# 09-USBUart_PPSMUX_UARTMUX.net
KiCad netlist of a schematic drawn in Altium Designer
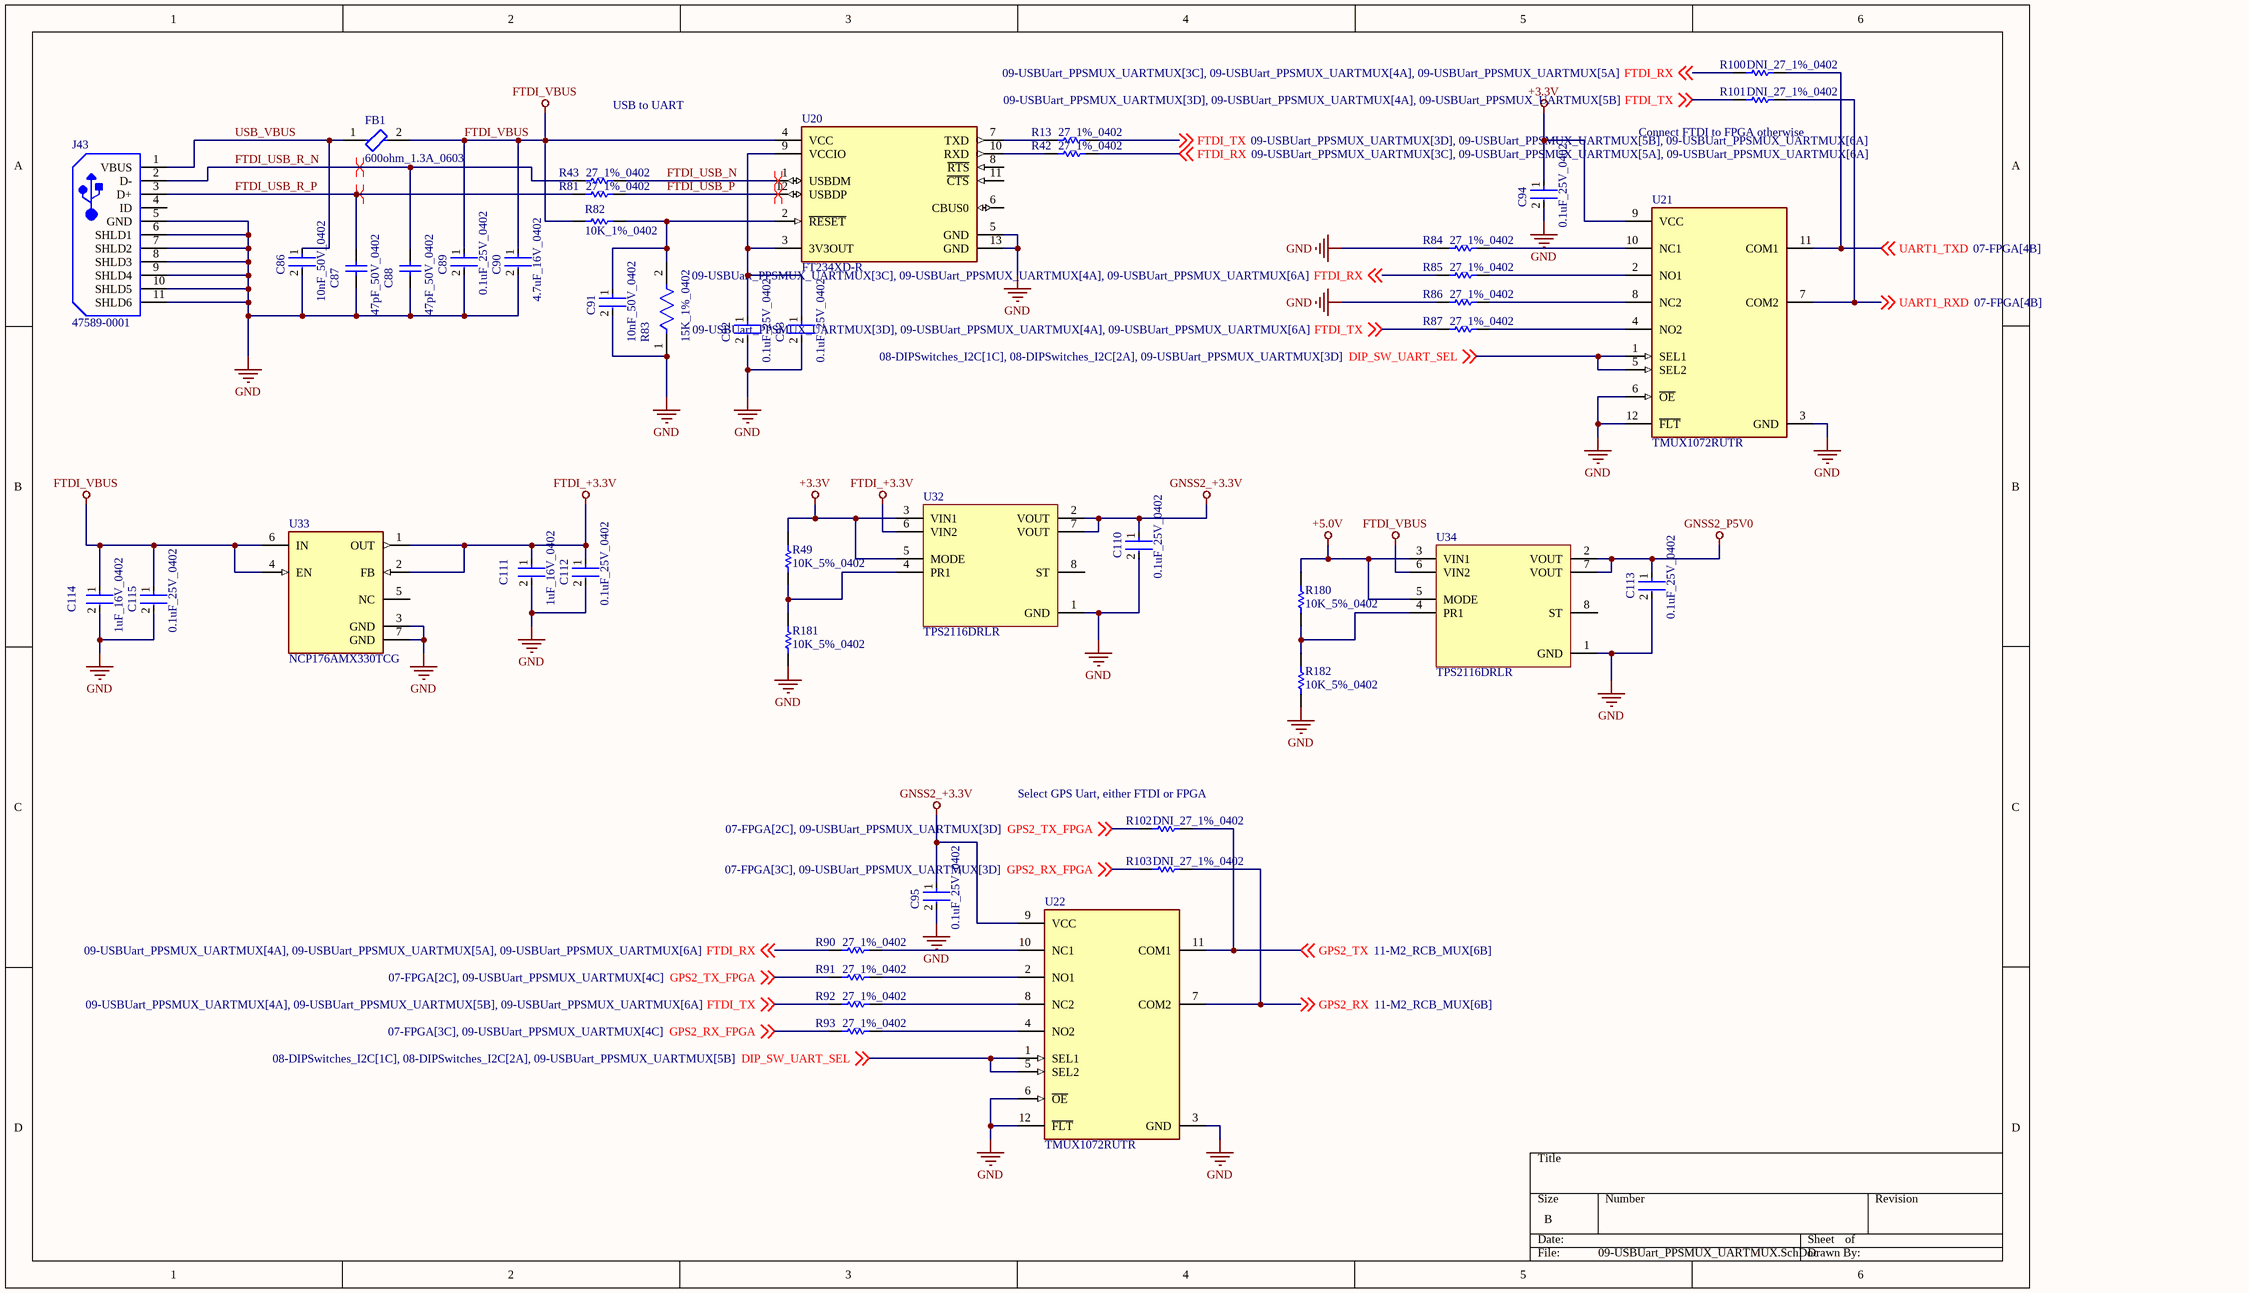
[diagram p0: 09-USBUart_PPSMUX_UARTMUX.SchDoc]

(export (version "E")
  (design (tool "Eeschema 10.0.6"))
  (components
    (comp (ref "C86")
      (value "10nF_50V_0402")
      (footprint "FP-CC0402-MFG")
      (description "CAP CER 10000PF 50V X7R 0402")
      (fields
        (field (name "OCTOPART") "https://octopart.com/cc0402krx7r9bb103-yageo-8376513")
        (field (name "MANUFACTURER PART NUMBER") "CC0402KRX7R9BB103")
      )
      (libsource (lib "Altium Content Vault") (part "11868f565c42a9108669ba33697ecf6"))
    )
    (comp (ref "C87")
      (value "47pF_50V_0402")
      (footprint "CAPC1005X55X25LL05T10")
      (fields (field (name "PART NUMBER") "GRM1555C1H470JA01D") (field (name "MANUFACTURER") "Murata"))
      (libsource (lib "Altium Content Vault") (part "CAP"))
    )
    (comp (ref "C88")
      (value "47pF_50V_0402")
      (footprint "CAPC1005X55X25LL05T10")
      (fields (field (name "PART NUMBER") "GRM1555C1H470JA01D") (field (name "MANUFACTURER") "Murata"))
      (libsource (lib "Altium Content Vault") (part "CAP"))
    )
    (comp (ref "C89")
      (value "0.1uF_25V_0402")
      (footprint "FP-0402-L_1_0_1-W_0_5_0_1-IPC_C")
      (description "General Purpose Ceramic Capacitor, 0402, 100nF, 10%, X7R, 15%, 25V")
      (fields (field (name "VOLTAGE") "25V") (field (name "TOLERANCE") "10%"))
      (libsource (lib "Altium Content Vault") (part "b4654b650e69147ec39a6b967a45e02"))
    )
    (comp (ref "C90")
      (value "4.7uF_16V_0402")
      (footprint "FP-CL829-IPC_C")
      (description "Cap Ceramic 4.7uF 16V X5R ±20% SMD 0402 +85°C Paper T/R")
      (fields (field (name "TOLERANCE") "20%"))
      (libsource (lib "Altium Content Vault") (part "b4654b650e69147ec39a6b967a45e02"))
    )
    (comp (ref "C91")
      (value "10nF_50V_0402")
      (footprint "FP-CC0402-MFG")
      (description "CAP CER 10000PF 50V X7R 0402")
      (fields
        (field (name "OCTOPART") "https://octopart.com/cc0402krx7r9bb103-yageo-8376513")
        (field (name "MANUFACTURER PART NUMBER") "CC0402KRX7R9BB103")
      )
      (libsource (lib "Altium Content Vault") (part "11868f565c42a9108669ba33697ecf6"))
    )
    (comp (ref "C92")
      (value "0.1uF_25V_0402")
      (footprint "FP-0402-L_1_0_1-W_0_5_0_1-IPC_C")
      (description "General Purpose Ceramic Capacitor, 0402, 100nF, 10%, X7R, 15%, 25V")
      (fields (field (name "VOLTAGE") "25V") (field (name "TOLERANCE") "10%"))
      (libsource (lib "Altium Content Vault") (part "b4654b650e69147ec39a6b967a45e02"))
    )
    (comp (ref "C93")
      (value "0.1uF_25V_0402")
      (footprint "FP-0402-L_1_0_1-W_0_5_0_1-IPC_C")
      (description "General Purpose Ceramic Capacitor, 0402, 100nF, 10%, X7R, 15%, 25V")
      (fields (field (name "VOLTAGE") "25V") (field (name "TOLERANCE") "10%"))
      (libsource (lib "Altium Content Vault") (part "b4654b650e69147ec39a6b967a45e02"))
    )
    (comp (ref "C94")
      (value "0.1uF_25V_0402")
      (footprint "FP-0402-L_1_0_1-W_0_5_0_1-IPC_C")
      (description "General Purpose Ceramic Capacitor, 0402, 100nF, 10%, X7R, 15%, 25V")
      (fields (field (name "VOLTAGE") "25V") (field (name "TOLERANCE") "10%"))
      (libsource (lib "Altium Content Vault") (part "b4654b650e69147ec39a6b967a45e02"))
    )
    (comp (ref "C95")
      (value "0.1uF_25V_0402")
      (footprint "FP-0402-L_1_0_1-W_0_5_0_1-IPC_C")
      (description "General Purpose Ceramic Capacitor, 0402, 100nF, 10%, X7R, 15%, 25V")
      (fields (field (name "VOLTAGE") "25V") (field (name "TOLERANCE") "10%"))
      (libsource (lib "Altium Content Vault") (part "b4654b650e69147ec39a6b967a45e02"))
    )
    (comp (ref "C110")
      (value "0.1uF_25V_0402")
      (footprint "FP-0402-L_1_0_1-W_0_5_0_1-IPC_C")
      (description "General Purpose Ceramic Capacitor, 0402, 100nF, 10%, X7R, 15%, 25V")
      (fields (field (name "VOLTAGE") "25V") (field (name "TOLERANCE") "10%"))
      (libsource (lib "Altium Content Vault") (part "b4654b650e69147ec39a6b967a45e02"))
    )
    (comp (ref "C111")
      (value "1uF_16V_0402")
      (footprint "FP-0402-L_1_0_0_05-W_0_5-IPC_A")
      (description "None")
      (fields (field (name "TOLERANCE") "10%"))
      (libsource (lib "Altium Content Vault") (part "b4654b650e69147ec39a6b967a45e02"))
    )
    (comp (ref "C112")
      (value "0.1uF_25V_0402")
      (footprint "FP-0402-L_1_0_1-W_0_5_0_1-IPC_C")
      (description "General Purpose Ceramic Capacitor, 0402, 100nF, 10%, X7R, 15%, 25V")
      (fields (field (name "VOLTAGE") "25V") (field (name "TOLERANCE") "10%"))
      (libsource (lib "Altium Content Vault") (part "b4654b650e69147ec39a6b967a45e02"))
    )
    (comp (ref "C113")
      (value "0.1uF_25V_0402")
      (footprint "FP-0402-L_1_0_1-W_0_5_0_1-IPC_C")
      (description "General Purpose Ceramic Capacitor, 0402, 100nF, 10%, X7R, 15%, 25V")
      (fields (field (name "VOLTAGE") "25V") (field (name "TOLERANCE") "10%"))
      (libsource (lib "Altium Content Vault") (part "b4654b650e69147ec39a6b967a45e02"))
    )
    (comp (ref "C114")
      (value "1uF_16V_0402")
      (footprint "FP-0402-L_1_0_0_05-W_0_5-IPC_A")
      (description "None")
      (fields (field (name "TOLERANCE") "10%"))
      (libsource (lib "Altium Content Vault") (part "b4654b650e69147ec39a6b967a45e02"))
    )
    (comp (ref "C115")
      (value "0.1uF_25V_0402")
      (footprint "FP-0402-L_1_0_1-W_0_5_0_1-IPC_C")
      (description "General Purpose Ceramic Capacitor, 0402, 100nF, 10%, X7R, 15%, 25V")
      (fields (field (name "VOLTAGE") "25V") (field (name "TOLERANCE") "10%"))
      (libsource (lib "Altium Content Vault") (part "b4654b650e69147ec39a6b967a45e02"))
    )
    (comp (ref "FB1")
      (value "600ohm_1.3A_0603")
      (footprint "FP-BLM18-0_15-t0_8-IPC_A")
      (description "Chip Ferrite Bead, 0603, 600Ω @ 100MHz, 0.15Ω, 25%, 1.3A")
      (fields (field (name "TOLERANCE") "25%"))
      (libsource (lib "Altium Content Vault") (part "5f30dd21d616792df468990f7003faa"))
    )
    (comp (ref "J43")
      (value "47589-0001")
      (footprint "MOLX-47589-0001_V")
      (description "Right Angle Female Type AB Micro USB Connector, 30 V, 1.8 A, -30 to 85 degC, RoHS, Tape and Reel")
      (fields (field (name "MANUFACTURER") "Molex"))
      (libsource (lib "Altium Content Vault") (part "USB-5-6SHLD"))
    )
    (comp (ref "R13")
      (value "27_1%_0402")
      (footprint "RESC1005X40X25NL05T05")
      (fields (field (name "PART NUMBER") "CRCW040227R0FKED") (field (name "MANUFACTURER") "Vishay Dale"))
      (libsource (lib "Altium Content Vault") (part "RES"))
    )
    (comp (ref "R42")
      (value "27_1%_0402")
      (footprint "RESC1005X40X25NL05T05")
      (fields (field (name "PART NUMBER") "CRCW040227R0FKED") (field (name "MANUFACTURER") "Vishay Dale"))
      (libsource (lib "Altium Content Vault") (part "RES"))
    )
    (comp (ref "R43")
      (value "27_1%_0402")
      (footprint "RESC1005X40X25NL05T05")
      (fields (field (name "PART NUMBER") "CRCW040227R0FKED") (field (name "MANUFACTURER") "Vishay Dale"))
      (libsource (lib "Altium Content Vault") (part "RES"))
    )
    (comp (ref "R49")
      (value "10K_5%_0402")
      (footprint "RESC1005X40X25ML05T05")
      (fields (field (name "PART NUMBER") "ERJ-2GEJ103X") (field (name "MANUFACTURER") "Panasonic"))
      (libsource (lib "Altium Content Vault") (part "RES"))
    )
    (comp (ref "R81")
      (value "27_1%_0402")
      (footprint "RESC1005X40X25NL05T05")
      (fields (field (name "PART NUMBER") "CRCW040227R0FKED") (field (name "MANUFACTURER") "Vishay Dale"))
      (libsource (lib "Altium Content Vault") (part "RES"))
    )
    (comp (ref "R82")
      (value "10K_1%_0402")
      (footprint "RESC1005X40X25LL05T10")
      (fields (field (name "PART NUMBER") "RC0402FR-0710KL") (field (name "MANUFACTURER") "Yageo / Phycomp"))
      (libsource (lib "Altium Content Vault") (part "RES"))
    )
    (comp (ref "R83")
      (value "15K_1%_0402")
      (footprint "FP-ERJ2R-MFG")
      (description "RES SMD 15K OHM 1% 1/10W 0402")
      (fields (field (name "TOLERANCE") "1%") (field (name "MANUFACTURER PART NUMBER") "ERJ-2RKF1502X"))
      (libsource (lib "Altium Content Vault") (part "1029c3af85768c4190bb7ad29bc67b5"))
    )
    (comp (ref "R84")
      (value "27_1%_0402")
      (footprint "RESC1005X40X25NL05T05")
      (fields (field (name "PART NUMBER") "CRCW040227R0FKED") (field (name "MANUFACTURER") "Vishay Dale"))
      (libsource (lib "Altium Content Vault") (part "RES"))
    )
    (comp (ref "R85")
      (value "27_1%_0402")
      (footprint "RESC1005X40X25NL05T05")
      (fields (field (name "PART NUMBER") "CRCW040227R0FKED") (field (name "MANUFACTURER") "Vishay Dale"))
      (libsource (lib "Altium Content Vault") (part "RES"))
    )
    (comp (ref "R86")
      (value "27_1%_0402")
      (footprint "RESC1005X40X25NL05T05")
      (fields (field (name "PART NUMBER") "CRCW040227R0FKED") (field (name "MANUFACTURER") "Vishay Dale"))
      (libsource (lib "Altium Content Vault") (part "RES"))
    )
    (comp (ref "R87")
      (value "27_1%_0402")
      (footprint "RESC1005X40X25NL05T05")
      (fields (field (name "PART NUMBER") "CRCW040227R0FKED") (field (name "MANUFACTURER") "Vishay Dale"))
      (libsource (lib "Altium Content Vault") (part "RES"))
    )
    (comp (ref "R90")
      (value "27_1%_0402")
      (footprint "RESC1005X40X25NL05T05")
      (fields (field (name "PART NUMBER") "CRCW040227R0FKED") (field (name "MANUFACTURER") "Vishay Dale"))
      (libsource (lib "Altium Content Vault") (part "RES"))
    )
    (comp (ref "R91")
      (value "27_1%_0402")
      (footprint "RESC1005X40X25NL05T05")
      (fields (field (name "PART NUMBER") "CRCW040227R0FKED") (field (name "MANUFACTURER") "Vishay Dale"))
      (libsource (lib "Altium Content Vault") (part "RES"))
    )
    (comp (ref "R92")
      (value "27_1%_0402")
      (footprint "RESC1005X40X25NL05T05")
      (fields (field (name "PART NUMBER") "CRCW040227R0FKED") (field (name "MANUFACTURER") "Vishay Dale"))
      (libsource (lib "Altium Content Vault") (part "RES"))
    )
    (comp (ref "R93")
      (value "27_1%_0402")
      (footprint "RESC1005X40X25NL05T05")
      (fields (field (name "PART NUMBER") "CRCW040227R0FKED") (field (name "MANUFACTURER") "Vishay Dale"))
      (libsource (lib "Altium Content Vault") (part "RES"))
    )
    (comp (ref "R100")
      (value "DNI_27_1%_0402")
      (footprint "RESC1005X40X25NL05T05")
      (fields (field (name "PART NUMBER") "CRCW040227R0FKED") (field (name "MANUFACTURER") "Vishay Dale"))
      (libsource (lib "Altium Content Vault") (part "RES"))
    )
    (comp (ref "R101")
      (value "DNI_27_1%_0402")
      (footprint "RESC1005X40X25NL05T05")
      (fields (field (name "PART NUMBER") "CRCW040227R0FKED") (field (name "MANUFACTURER") "Vishay Dale"))
      (libsource (lib "Altium Content Vault") (part "RES"))
    )
    (comp (ref "R102")
      (value "DNI_27_1%_0402")
      (footprint "RESC1005X40X25NL05T05")
      (fields (field (name "PART NUMBER") "CRCW040227R0FKED") (field (name "MANUFACTURER") "Vishay Dale"))
      (libsource (lib "Altium Content Vault") (part "RES"))
    )
    (comp (ref "R103")
      (value "DNI_27_1%_0402")
      (footprint "RESC1005X40X25NL05T05")
      (fields (field (name "PART NUMBER") "CRCW040227R0FKED") (field (name "MANUFACTURER") "Vishay Dale"))
      (libsource (lib "Altium Content Vault") (part "RES"))
    )
    (comp (ref "R180")
      (value "10K_5%_0402")
      (footprint "RESC1005X40X25ML05T05")
      (fields (field (name "PART NUMBER") "ERJ-2GEJ103X") (field (name "MANUFACTURER") "Panasonic"))
      (libsource (lib "Altium Content Vault") (part "RES"))
    )
    (comp (ref "R181")
      (value "10K_5%_0402")
      (footprint "RESC1005X40X25ML05T05")
      (fields (field (name "PART NUMBER") "ERJ-2GEJ103X") (field (name "MANUFACTURER") "Panasonic"))
      (libsource (lib "Altium Content Vault") (part "RES"))
    )
    (comp (ref "R182")
      (value "10K_5%_0402")
      (footprint "RESC1005X40X25ML05T05")
      (fields (field (name "PART NUMBER") "ERJ-2GEJ103X") (field (name "MANUFACTURER") "Panasonic"))
      (libsource (lib "Altium Content Vault") (part "RES"))
    )
    (comp (ref "U20")
      (value "FT234XD-R")
      (footprint "FP-DFN-12-IPC_B")
      (description "IC USB SERIAL BASIC UART 12DFN")
      (libsource (lib "Altium Content Vault") (part "4bef3367ed9f9051bcb84ab46edda1c"))
    )
    (comp (ref "U21")
      (value "TMUX1072RUTR")
      (footprint "FP-RUT0012A-MFG")
      (description "IC SWITCH SPDT DUAL 12UQFN")
      (libsource (lib "Altium Content Vault") (part "12a319ab100cd6cfe745e35972674f5"))
    )
    (comp (ref "U22")
      (value "TMUX1072RUTR")
      (footprint "FP-RUT0012A-MFG")
      (description "IC SWITCH SPDT DUAL 12UQFN")
      (libsource (lib "Altium Content Vault") (part "12a319ab100cd6cfe745e35972674f5"))
    )
    (comp (ref "U32")
      (value "TPS2116DRLR")
      (footprint "IC_TPS2116")
      (description "1.6-V to 5.5-V, 40-mΩ, 2.5-A, low-IQ, priority power multiplexer 8-SOT-5X3 -40 to 125")
      (fields (field (name "MF") "Texas Instruments"))
      (libsource (lib "LotusSound") (part "IC_TPS2116DRLR"))
    )
    (comp (ref "U33")
      (value "NCP176AMX330TCG")
      (footprint "FP-711AT-MFG")
      (description "IC REG LINEAR 3.3V 500MA 6XDFN")
      (fields
        (field (name "MANUFACTURER") "ON Semiconductor")
        (field (name "OCTOPART") "https://octopart.com/ncp176amx330tcg-on+semiconductor-61522616")
      )
      (libsource (lib "Altium Content Vault") (part "a38d0f79c2a9f01c07a7e52882ed186"))
    )
    (comp (ref "U34")
      (value "TPS2116DRLR")
      (footprint "IC_TPS2116")
      (description "1.6-V to 5.5-V, 40-mΩ, 2.5-A, low-IQ, priority power multiplexer 8-SOT-5X3 -40 to 125")
      (fields (field (name "MF") "Texas Instruments"))
      (libsource (lib "LotusSound") (part "IC_TPS2116DRLR"))
    )
  )
  (nets
    (net (code "1") (name "+3.3V") (class "Default")
      (node (ref "C94") (pin "1") (pinfunction "1_1") (pintype "passive"))
      (node (ref "R49") (pin "2") (pinfunction "2_2") (pintype "passive"))
      (node (ref "U21") (pin "9") (pinfunction "VCC_9") (pintype "power_in"))
      (node (ref "U32") (pin "3") (pinfunction "VIN1_3") (pintype "passive"))
      (node (ref "U32") (pin "5") (pinfunction "MODE_5") (pintype "passive"))
    )
    (net (code "2") (name "+5.0V") (class "Default")
      (node (ref "R180") (pin "2") (pinfunction "2_2") (pintype "passive"))
      (node (ref "U34") (pin "3") (pinfunction "VIN1_3") (pintype "passive"))
      (node (ref "U34") (pin "5") (pinfunction "MODE_5") (pintype "passive"))
    )
    (net (code "3") (name "/FTDI_USB_N") (class "Default")
      (node (ref "R43") (pin "2") (pinfunction "2_2") (pintype "passive"))
      (node (ref "U20") (pin "1") (pinfunction "USBDM_1") (pintype "bidirectional"))
    )
    (net (code "4") (name "/FTDI_USB_P") (class "Default")
      (node (ref "R81") (pin "2") (pinfunction "2_2") (pintype "passive"))
      (node (ref "U20") (pin "12") (pinfunction "USBDP_12") (pintype "bidirectional"))
    )
    (net (code "5") (name "/FTDI_USB_R_N") (class "Default")
      (node (ref "C88") (pin "2") (pinfunction "2_2") (pintype "passive"))
      (node (ref "J43") (pin "2") (pinfunction "D-_2") (pintype "passive"))
      (node (ref "R43") (pin "1") (pinfunction "1_1") (pintype "passive"))
    )
    (net (code "6") (name "/FTDI_USB_R_P") (class "Default")
      (node (ref "C87") (pin "2") (pinfunction "2_2") (pintype "passive"))
      (node (ref "J43") (pin "3") (pinfunction "D+_3") (pintype "passive"))
      (node (ref "R81") (pin "1") (pinfunction "1_1") (pintype "passive"))
    )
    (net (code "7") (name "/USB_VBUS") (class "Default")
      (node (ref "C86") (pin "1") (pinfunction "1_1") (pintype "passive"))
      (node (ref "FB1") (pin "1") (pinfunction "1_1") (pintype "passive"))
      (node (ref "J43") (pin "1") (pinfunction "VBUS_1") (pintype "passive"))
    )
    (net (code "8") (name "DIP_SW_UART_SEL") (class "Default")
      (node (ref "U21") (pin "1") (pinfunction "SEL1_1") (pintype "input"))
      (node (ref "U21") (pin "5") (pinfunction "SEL2_5") (pintype "input"))
      (node (ref "U22") (pin "1") (pinfunction "SEL1_1") (pintype "input"))
      (node (ref "U22") (pin "5") (pinfunction "SEL2_5") (pintype "input"))
    )
    (net (code "9") (name "FTDI_+3.3V") (class "Default")
      (node (ref "C111") (pin "1") (pinfunction "1_1") (pintype "passive"))
      (node (ref "C112") (pin "1") (pinfunction "1_1") (pintype "passive"))
      (node (ref "U32") (pin "6") (pinfunction "VIN2_6") (pintype "passive"))
      (node (ref "U33") (pin "1") (pinfunction "OUT_1") (pintype "output"))
      (node (ref "U33") (pin "2") (pinfunction "FB_2") (pintype "input"))
    )
    (net (code "10") (name "FTDI_RX") (class "Default")
      (node (ref "R100") (pin "1") (pinfunction "1_1") (pintype "passive"))
      (node (ref "R42") (pin "2") (pinfunction "2_2") (pintype "passive"))
      (node (ref "R85") (pin "1") (pinfunction "1_1") (pintype "passive"))
      (node (ref "R90") (pin "1") (pinfunction "1_1") (pintype "passive"))
    )
    (net (code "11") (name "FTDI_TX") (class "Default")
      (node (ref "R101") (pin "1") (pinfunction "1_1") (pintype "passive"))
      (node (ref "R13") (pin "2") (pinfunction "2_2") (pintype "passive"))
      (node (ref "R87") (pin "1") (pinfunction "1_1") (pintype "passive"))
      (node (ref "R92") (pin "1") (pinfunction "1_1") (pintype "passive"))
    )
    (net (code "12") (name "FTDI_VBUS") (class "Default")
      (node (ref "C114") (pin "1") (pinfunction "1_1") (pintype "passive"))
      (node (ref "C115") (pin "1") (pinfunction "1_1") (pintype "passive"))
      (node (ref "C89") (pin "1") (pinfunction "1_1") (pintype "passive"))
      (node (ref "C90") (pin "1") (pinfunction "1_1") (pintype "passive"))
      (node (ref "FB1") (pin "2") (pinfunction "2_2") (pintype "passive"))
      (node (ref "R82") (pin "2") (pinfunction "2_2") (pintype "passive"))
      (node (ref "U20") (pin "4") (pinfunction "VCC_4") (pintype "power_in"))
      (node (ref "U33") (pin "4") (pinfunction "EN_4") (pintype "input"))
      (node (ref "U33") (pin "6") (pinfunction "IN_6") (pintype "power_in"))
      (node (ref "U34") (pin "6") (pinfunction "VIN2_6") (pintype "passive"))
    )
    (net (code "13") (name "GND") (class "Default")
      (node (ref "C110") (pin "2") (pinfunction "2_2") (pintype "passive"))
      (node (ref "C111") (pin "2") (pinfunction "2_2") (pintype "passive"))
      (node (ref "C112") (pin "2") (pinfunction "2_2") (pintype "passive"))
      (node (ref "C113") (pin "2") (pinfunction "2_2") (pintype "passive"))
      (node (ref "C114") (pin "2") (pinfunction "2_2") (pintype "passive"))
      (node (ref "C115") (pin "2") (pinfunction "2_2") (pintype "passive"))
      (node (ref "C86") (pin "2") (pinfunction "2_2") (pintype "passive"))
      (node (ref "C87") (pin "1") (pinfunction "1_1") (pintype "passive"))
      (node (ref "C88") (pin "1") (pinfunction "1_1") (pintype "passive"))
      (node (ref "C89") (pin "2") (pinfunction "2_2") (pintype "passive"))
      (node (ref "C90") (pin "2") (pinfunction "2_2") (pintype "passive"))
      (node (ref "C91") (pin "2") (pinfunction "2_2") (pintype "passive"))
      (node (ref "C92") (pin "2") (pinfunction "2_2") (pintype "passive"))
      (node (ref "C93") (pin "2") (pinfunction "2_2") (pintype "passive"))
      (node (ref "C94") (pin "2") (pinfunction "2_2") (pintype "passive"))
      (node (ref "C95") (pin "2") (pinfunction "2_2") (pintype "passive"))
      (node (ref "J43") (pin "10") (pinfunction "SHLD5_10") (pintype "passive"))
      (node (ref "J43") (pin "11") (pinfunction "SHLD6_11") (pintype "passive"))
      (node (ref "J43") (pin "5") (pinfunction "GND_5") (pintype "passive"))
      (node (ref "J43") (pin "6") (pinfunction "SHLD1_6") (pintype "passive"))
      (node (ref "J43") (pin "7") (pinfunction "SHLD2_7") (pintype "passive"))
      (node (ref "J43") (pin "8") (pinfunction "SHLD3_8") (pintype "passive"))
      (node (ref "J43") (pin "9") (pinfunction "SHLD4_9") (pintype "passive"))
      (node (ref "R181") (pin "1") (pinfunction "1_1") (pintype "passive"))
      (node (ref "R182") (pin "1") (pinfunction "1_1") (pintype "passive"))
      (node (ref "R83") (pin "1") (pinfunction "1_1") (pintype "passive"))
      (node (ref "R84") (pin "1") (pinfunction "1_1") (pintype "passive"))
      (node (ref "R86") (pin "1") (pinfunction "1_1") (pintype "passive"))
      (node (ref "U20") (pin "13") (pinfunction "GND_13") (pintype "power_in"))
      (node (ref "U20") (pin "5") (pinfunction "GND_5") (pintype "power_in"))
      (node (ref "U21") (pin "12") (pinfunction "~{FLT}_12") (pintype "open_collector"))
      (node (ref "U21") (pin "3") (pinfunction "GND_3") (pintype "power_in"))
      (node (ref "U21") (pin "6") (pinfunction "~{OE}_6") (pintype "input"))
      (node (ref "U22") (pin "12") (pinfunction "~{FLT}_12") (pintype "open_collector"))
      (node (ref "U22") (pin "3") (pinfunction "GND_3") (pintype "power_in"))
      (node (ref "U22") (pin "6") (pinfunction "~{OE}_6") (pintype "input"))
      (node (ref "U32") (pin "1") (pinfunction "GND_1") (pintype "passive"))
      (node (ref "U33") (pin "3") (pinfunction "GND_3") (pintype "power_in"))
      (node (ref "U33") (pin "7") (pinfunction "GND_7") (pintype "power_in"))
      (node (ref "U34") (pin "1") (pinfunction "GND_1") (pintype "passive"))
    )
    (net (code "14") (name "GNSS2_+3.3V") (class "Default")
      (node (ref "C110") (pin "1") (pinfunction "1_1") (pintype "passive"))
      (node (ref "C95") (pin "1") (pinfunction "1_1") (pintype "passive"))
      (node (ref "U22") (pin "9") (pinfunction "VCC_9") (pintype "power_in"))
      (node (ref "U32") (pin "2") (pinfunction "VOUT_2") (pintype "passive"))
      (node (ref "U32") (pin "7") (pinfunction "VOUT_7") (pintype "passive"))
    )
    (net (code "15") (name "GNSS2_P5V0") (class "Default")
      (node (ref "C113") (pin "1") (pinfunction "1_1") (pintype "passive"))
      (node (ref "U34") (pin "2") (pinfunction "VOUT_2") (pintype "passive"))
      (node (ref "U34") (pin "7") (pinfunction "VOUT_7") (pintype "passive"))
    )
    (net (code "16") (name "GPS2_RX") (class "Default")
      (node (ref "R103") (pin "2") (pinfunction "2_2") (pintype "passive"))
      (node (ref "U22") (pin "7") (pinfunction "COM2_7") (pintype "passive"))
    )
    (net (code "17") (name "GPS2_RX_FPGA") (class "Default")
      (node (ref "R103") (pin "1") (pinfunction "1_1") (pintype "passive"))
      (node (ref "R93") (pin "1") (pinfunction "1_1") (pintype "passive"))
    )
    (net (code "18") (name "GPS2_TX") (class "Default")
      (node (ref "R102") (pin "2") (pinfunction "2_2") (pintype "passive"))
      (node (ref "U22") (pin "11") (pinfunction "COM1_11") (pintype "passive"))
    )
    (net (code "19") (name "GPS2_TX_FPGA") (class "Default")
      (node (ref "R102") (pin "1") (pinfunction "1_1") (pintype "passive"))
      (node (ref "R91") (pin "1") (pinfunction "1_1") (pintype "passive"))
    )
    (net (code "20") (name "Net-(U20-3V3OUT)") (class "Default")
      (node (ref "C92") (pin "1") (pinfunction "1_1") (pintype "passive"))
      (node (ref "C93") (pin "1") (pinfunction "1_1") (pintype "passive"))
      (node (ref "U20") (pin "3") (pinfunction "3V3OUT_3") (pintype "power_in"))
      (node (ref "U20") (pin "9") (pinfunction "VCCIO_9") (pintype "power_in"))
    )
    (net (code "21") (name "Net-(U20-RXD)") (class "Default")
      (node (ref "R42") (pin "1") (pinfunction "1_1") (pintype "passive"))
      (node (ref "U20") (pin "10") (pinfunction "RXD_10") (pintype "output"))
    )
    (net (code "22") (name "Net-(U20-TXD)") (class "Default")
      (node (ref "R13") (pin "1") (pinfunction "1_1") (pintype "passive"))
      (node (ref "U20") (pin "7") (pinfunction "TXD_7") (pintype "output"))
    )
    (net (code "23") (name "Net-(U20-~{RESET})") (class "Default")
      (node (ref "C91") (pin "1") (pinfunction "1_1") (pintype "passive"))
      (node (ref "R82") (pin "1") (pinfunction "1_1") (pintype "passive"))
      (node (ref "R83") (pin "2") (pinfunction "2_2") (pintype "passive"))
      (node (ref "U20") (pin "2") (pinfunction "~{RESET}_2") (pintype "input"))
    )
    (net (code "24") (name "Net-(U21-NC1)") (class "Default")
      (node (ref "R84") (pin "2") (pinfunction "2_2") (pintype "passive"))
      (node (ref "U21") (pin "10") (pinfunction "NC1_10") (pintype "passive"))
    )
    (net (code "25") (name "Net-(U21-NC2)") (class "Default")
      (node (ref "R86") (pin "2") (pinfunction "2_2") (pintype "passive"))
      (node (ref "U21") (pin "8") (pinfunction "NC2_8") (pintype "passive"))
    )
    (net (code "26") (name "Net-(U21-NO1)") (class "Default")
      (node (ref "R85") (pin "2") (pinfunction "2_2") (pintype "passive"))
      (node (ref "U21") (pin "2") (pinfunction "NO1_2") (pintype "passive"))
    )
    (net (code "27") (name "Net-(U21-NO2)") (class "Default")
      (node (ref "R87") (pin "2") (pinfunction "2_2") (pintype "passive"))
      (node (ref "U21") (pin "4") (pinfunction "NO2_4") (pintype "passive"))
    )
    (net (code "28") (name "Net-(U22-NC1)") (class "Default")
      (node (ref "R90") (pin "2") (pinfunction "2_2") (pintype "passive"))
      (node (ref "U22") (pin "10") (pinfunction "NC1_10") (pintype "passive"))
    )
    (net (code "29") (name "Net-(U22-NC2)") (class "Default")
      (node (ref "R92") (pin "2") (pinfunction "2_2") (pintype "passive"))
      (node (ref "U22") (pin "8") (pinfunction "NC2_8") (pintype "passive"))
    )
    (net (code "30") (name "Net-(U22-NO1)") (class "Default")
      (node (ref "R91") (pin "2") (pinfunction "2_2") (pintype "passive"))
      (node (ref "U22") (pin "2") (pinfunction "NO1_2") (pintype "passive"))
    )
    (net (code "31") (name "Net-(U22-NO2)") (class "Default")
      (node (ref "R93") (pin "2") (pinfunction "2_2") (pintype "passive"))
      (node (ref "U22") (pin "4") (pinfunction "NO2_4") (pintype "passive"))
    )
    (net (code "32") (name "Net-(U32-PR1)") (class "Default")
      (node (ref "R181") (pin "2") (pinfunction "2_2") (pintype "passive"))
      (node (ref "R49") (pin "1") (pinfunction "1_1") (pintype "passive"))
      (node (ref "U32") (pin "4") (pinfunction "PR1_4") (pintype "passive"))
    )
    (net (code "33") (name "Net-(U34-PR1)") (class "Default")
      (node (ref "R180") (pin "1") (pinfunction "1_1") (pintype "passive"))
      (node (ref "R182") (pin "2") (pinfunction "2_2") (pintype "passive"))
      (node (ref "U34") (pin "4") (pinfunction "PR1_4") (pintype "passive"))
    )
    (net (code "34") (name "UART1_RXD") (class "Default")
      (node (ref "R101") (pin "2") (pinfunction "2_2") (pintype "passive"))
      (node (ref "U21") (pin "7") (pinfunction "COM2_7") (pintype "passive"))
    )
    (net (code "35") (name "UART1_TXD") (class "Default")
      (node (ref "R100") (pin "2") (pinfunction "2_2") (pintype "passive"))
      (node (ref "U21") (pin "11") (pinfunction "COM1_11") (pintype "passive"))
    )
    (net (code "36") (name "unconnected-(J43-ID-Pad4)") (class "Default")
      (node (ref "J43") (pin "4") (pinfunction "ID_4") (pintype "passive"))
    )
    (net (code "37") (name "unconnected-(U20-CBUS0-Pad6)") (class "Default")
      (node (ref "U20") (pin "6") (pinfunction "CBUS0_6") (pintype "bidirectional"))
    )
    (net (code "38") (name "unconnected-(U20-~{CTS}-Pad11)") (class "Default")
      (node (ref "U20") (pin "11") (pinfunction "~{CTS}_11") (pintype "input"))
    )
    (net (code "39") (name "unconnected-(U20-~{RTS}-Pad8)") (class "Default")
      (node (ref "U20") (pin "8") (pinfunction "~{RTS}_8") (pintype "input"))
    )
    (net (code "40") (name "unconnected-(U32-ST-Pad8)") (class "Default")
      (node (ref "U32") (pin "8") (pinfunction "ST_8") (pintype "passive"))
    )
    (net (code "41") (name "unconnected-(U33-NC-Pad5)") (class "Default")
      (node (ref "U33") (pin "5") (pinfunction "NC_5") (pintype "passive"))
    )
    (net (code "42") (name "unconnected-(U34-ST-Pad8)") (class "Default")
      (node (ref "U34") (pin "8") (pinfunction "ST_8") (pintype "passive"))
    )
  )
)
